# untitled.net
KiCad netlist of a schematic drawn in EAGLE
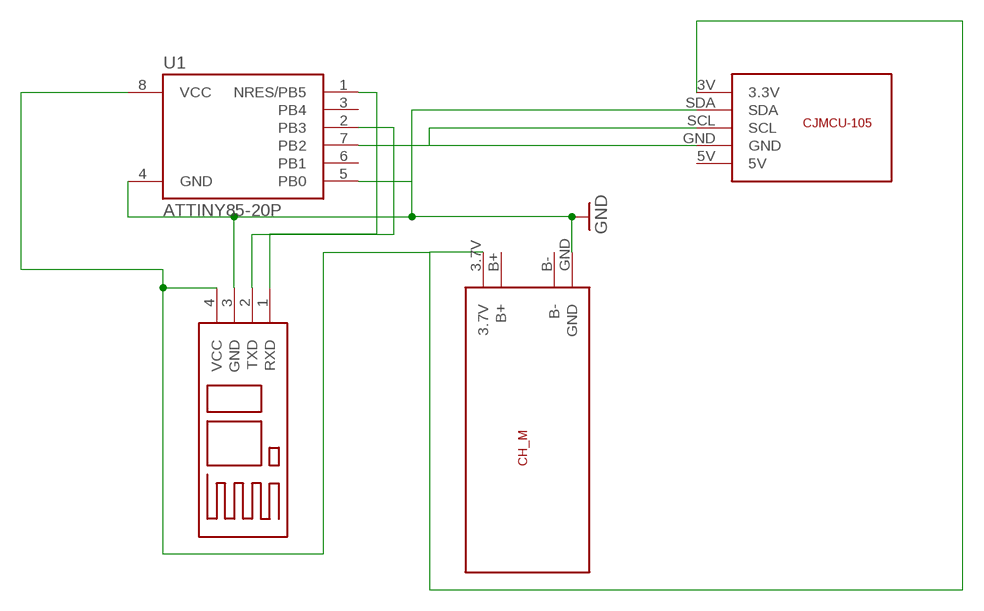
[diagram p0: schematic, sheet 1]

(export (version "E")
  (design (tool "Eeschema 10.0.6"))
  (components
    (comp (ref "B1")
      (value "BLUETOOTH")
      (footprint "eagle-import:BLUETOOTH")
      (libsource (lib "eagle-import") (part "BLUETOOTH"))
    )
    (comp (ref "U$1")
      (value "ADXLADXL")
      (footprint "eagle-import:CJMCU-105")
      (libsource (lib "eagle-import") (part "ADXLADXL"))
    )
    (comp (ref "U$2")
      (value "CH_MCH_M")
      (footprint "eagle-import:CHARGING_MODULE")
      (libsource (lib "eagle-import") (part "CH_MCH_M"))
    )
    (comp (ref "U1")
      (value "ATTINY85-20P")
      (footprint "eagle-import:PDIP08_300MIL")
      (libsource (lib "eagle-import") (part "ATTINY85P-20"))
    )
  )
  (nets
    (net (code "1") (name "GND") (class "Default")
      (node (ref "B1") (pin "3") (pinfunction "GND_3") (pintype "power_in"))
      (node (ref "U$1") (pin "GND") (pinfunction "GND_GND") (pintype "bidirectional"))
      (node (ref "U$2") (pin "GND") (pinfunction "GND_GND") (pintype "bidirectional"))
      (node (ref "U1") (pin "4") (pinfunction "GND_4") (pintype "power_in"))
    )
    (net (code "2") (name "Net-(B1-RXD)") (class "Default")
      (node (ref "B1") (pin "1") (pinfunction "RXD_1") (pintype "bidirectional"))
      (node (ref "U1") (pin "1") (pinfunction "NRES/PB5_1") (pintype "bidirectional"))
    )
    (net (code "3") (name "Net-(B1-TXD)") (class "Default")
      (node (ref "B1") (pin "2") (pinfunction "TXD_2") (pintype "bidirectional"))
      (node (ref "U1") (pin "2") (pinfunction "PB3_2") (pintype "bidirectional"))
    )
    (net (code "4") (name "Net-(B1-VCC)") (class "Default")
      (node (ref "B1") (pin "4") (pinfunction "VCC_4") (pintype "power_in"))
      (node (ref "U$1") (pin "3V") (pinfunction "3.3V_3V") (pintype "bidirectional"))
      (node (ref "U$2") (pin "3.7V") (pinfunction "3.7V_3.7V") (pintype "bidirectional"))
      (node (ref "U1") (pin "8") (pinfunction "VCC_8") (pintype "power_in"))
    )
    (net (code "5") (name "Net-(U1-PB0)") (class "Default")
      (node (ref "U$1") (pin "SDA") (pinfunction "SDA_SDA") (pintype "bidirectional"))
      (node (ref "U1") (pin "5") (pinfunction "PB0_5") (pintype "bidirectional"))
    )
    (net (code "6") (name "Net-(U1-PB2)") (class "Default")
      (node (ref "U$1") (pin "SCL") (pinfunction "SCL_SCL") (pintype "bidirectional"))
      (node (ref "U1") (pin "7") (pinfunction "PB2_7") (pintype "bidirectional"))
    )
    (net (code "7") (name "unconnected-(U$1-Pad5V)") (class "Default")
      (node (ref "U$1") (pin "5V") (pinfunction "5V_5V") (pintype "bidirectional"))
    )
    (net (code "8") (name "unconnected-(U$2-PadB+)") (class "Default")
      (node (ref "U$2") (pin "B+") (pinfunction "B+_B+") (pintype "bidirectional"))
    )
    (net (code "9") (name "unconnected-(U$2-PadB-)") (class "Default")
      (node (ref "U$2") (pin "B-") (pinfunction "B-_B-") (pintype "bidirectional"))
    )
    (net (code "10") (name "unconnected-(U1-PB1-Pad6)") (class "Default")
      (node (ref "U1") (pin "6") (pinfunction "PB1_6") (pintype "bidirectional"))
    )
    (net (code "11") (name "unconnected-(U1-PB4-Pad3)") (class "Default")
      (node (ref "U1") (pin "3") (pinfunction "PB4_3") (pintype "bidirectional"))
    )
  )
)
